# WebServer3.net
KiCad netlist of a schematic drawn in EAGLE
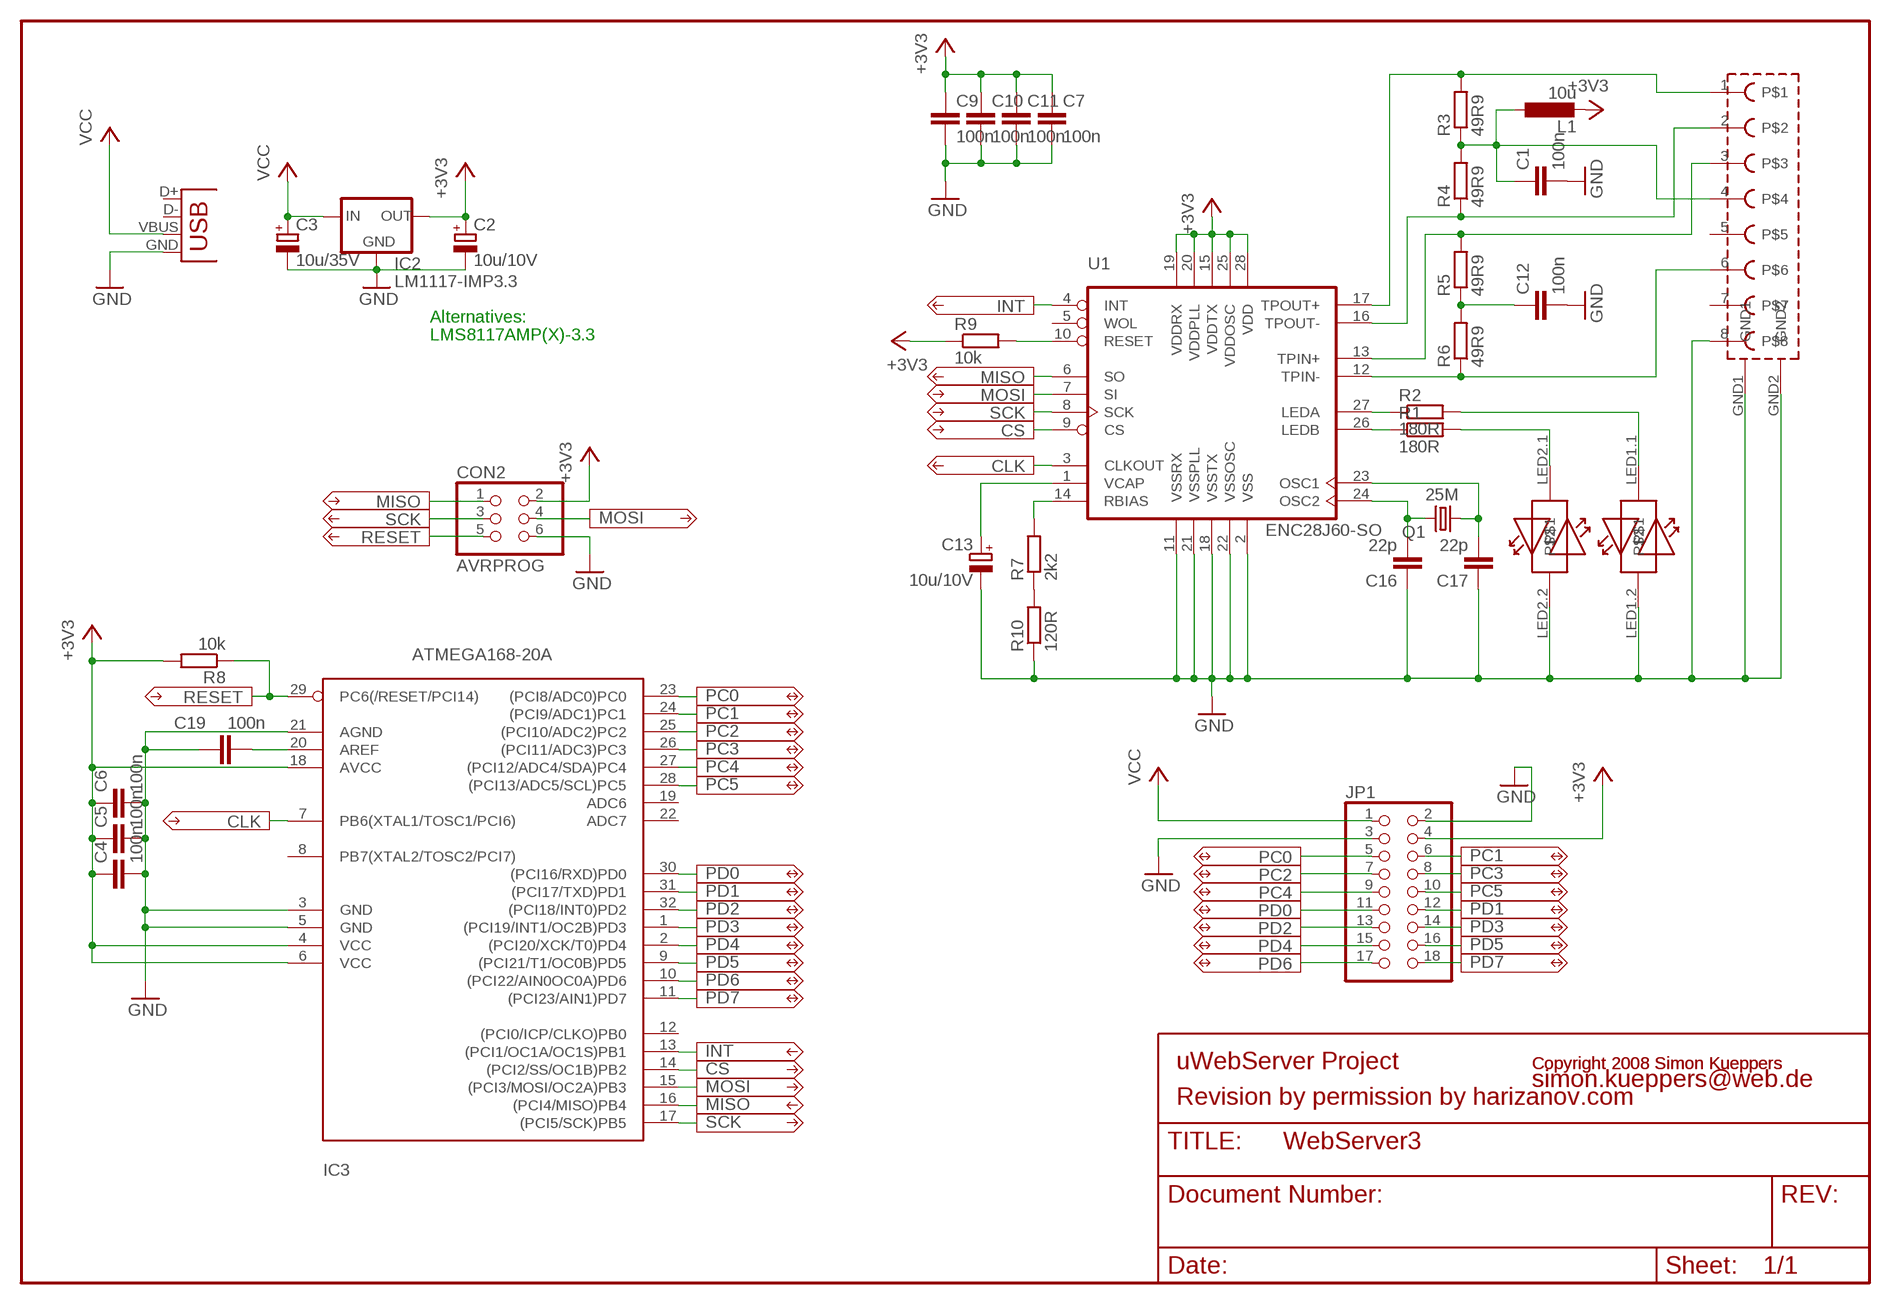
[diagram p0: schematic, sheet 1]

(export (version "E")
  (design (tool "Eeschema 10.0.6"))
  (components
    (comp (ref "C1")
      (value "100n")
      (footprint "eagle-import:C0805")
      (libsource (lib "eagle-import") (part "C-EUC0805"))
    )
    (comp (ref "C2")
      (value "10u/10V")
      (footprint "eagle-import:SMC_A")
      (libsource (lib "eagle-import") (part "CPOL-EUSMCA"))
    )
    (comp (ref "C3")
      (value "10u/35V")
      (footprint "eagle-import:SMC_C")
      (libsource (lib "eagle-import") (part "CPOL-EUSMCC"))
    )
    (comp (ref "C4")
      (value "100n")
      (footprint "eagle-import:C0805")
      (libsource (lib "eagle-import") (part "C-EUC0805"))
    )
    (comp (ref "C5")
      (value "100n")
      (footprint "eagle-import:C0805")
      (libsource (lib "eagle-import") (part "C-EUC0805"))
    )
    (comp (ref "C6")
      (value "100n")
      (footprint "eagle-import:C0805")
      (libsource (lib "eagle-import") (part "C-EUC0805"))
    )
    (comp (ref "C7")
      (value "100n")
      (footprint "eagle-import:C0805")
      (libsource (lib "eagle-import") (part "C-EUC0805"))
    )
    (comp (ref "C9")
      (value "100n")
      (footprint "eagle-import:C0805")
      (libsource (lib "eagle-import") (part "C-EUC0805"))
    )
    (comp (ref "C10")
      (value "100n")
      (footprint "eagle-import:C0805")
      (libsource (lib "eagle-import") (part "C-EUC0805"))
    )
    (comp (ref "C11")
      (value "100n")
      (footprint "eagle-import:C0805")
      (libsource (lib "eagle-import") (part "C-EUC0805"))
    )
    (comp (ref "C12")
      (value "100n")
      (footprint "eagle-import:C0805")
      (libsource (lib "eagle-import") (part "C-EUC0805"))
    )
    (comp (ref "C13")
      (value "10u/10V")
      (footprint "eagle-import:SMC_A")
      (libsource (lib "eagle-import") (part "CPOL-EUSMCA"))
    )
    (comp (ref "C16")
      (value "22p")
      (footprint "eagle-import:C0805")
      (libsource (lib "eagle-import") (part "C-EUC0805"))
    )
    (comp (ref "C17")
      (value "22p")
      (footprint "eagle-import:C0805")
      (libsource (lib "eagle-import") (part "C-EUC0805"))
    )
    (comp (ref "C19")
      (value "100n")
      (footprint "eagle-import:C0805")
      (libsource (lib "eagle-import") (part "C-EUC0805"))
    )
    (comp (ref "CON2")
      (value "AVRPROG")
      (footprint "eagle-import:2X03")
      (libsource (lib "eagle-import") (part "PINHD-2X3_2.54"))
    )
    (comp (ref "IC2")
      (value "LM1117-IMP3.3")
      (footprint "eagle-import:SOT223")
      (libsource (lib "eagle-import") (part "LM1117"))
    )
    (comp (ref "IC3")
      (value "ATMEGA168-20A")
      (footprint "eagle-import:TQFP32-08")
      (libsource (lib "eagle-import") (part "ATMEGA168A-20"))
    )
    (comp (ref "JP1")
      (value "PINHD-2X9")
      (footprint "eagle-import:2X09")
      (libsource (lib "eagle-import") (part "PINHD-2X9"))
    )
    (comp (ref "L1")
      (value "10u")
      (footprint "eagle-import:0207_10")
      (libsource (lib "eagle-import") (part "L-EU0207/10"))
    )
    (comp (ref "MAGJACK")
      (value "MAGJACK")
      (footprint "eagle-import:MAGJACK")
      (libsource (lib "eagle-import") (part "MAGJACK"))
    )
    (comp (ref "Q1")
      (value "25M")
      (footprint "eagle-import:HC49UP")
      (libsource (lib "eagle-import") (part "CRYSTALHC49UP"))
    )
    (comp (ref "R1")
      (value "180R")
      (footprint "eagle-import:R0805")
      (libsource (lib "eagle-import") (part "R-EU_R0805"))
    )
    (comp (ref "R2")
      (value "180R")
      (footprint "eagle-import:R0805")
      (libsource (lib "eagle-import") (part "R-EU_R0805"))
    )
    (comp (ref "R3")
      (value "49R9")
      (footprint "eagle-import:R0805")
      (libsource (lib "eagle-import") (part "R-EU_R0805"))
    )
    (comp (ref "R4")
      (value "49R9")
      (footprint "eagle-import:R0805")
      (libsource (lib "eagle-import") (part "R-EU_R0805"))
    )
    (comp (ref "R5")
      (value "49R9")
      (footprint "eagle-import:R0805")
      (libsource (lib "eagle-import") (part "R-EU_R0805"))
    )
    (comp (ref "R6")
      (value "49R9")
      (footprint "eagle-import:R0805")
      (libsource (lib "eagle-import") (part "R-EU_R0805"))
    )
    (comp (ref "R7")
      (value "2k2")
      (footprint "eagle-import:R0805")
      (libsource (lib "eagle-import") (part "R-EU_R0805"))
    )
    (comp (ref "R8")
      (value "10k")
      (footprint "eagle-import:R0805")
      (libsource (lib "eagle-import") (part "R-EU_R0805"))
    )
    (comp (ref "R9")
      (value "10k")
      (footprint "eagle-import:R0805")
      (libsource (lib "eagle-import") (part "R-EU_R0805"))
    )
    (comp (ref "R10")
      (value "120R")
      (footprint "eagle-import:R0805")
      (libsource (lib "eagle-import") (part "R-EU_R0805"))
    )
    (comp (ref "U1")
      (value "ENC28J60-SO")
      (footprint "eagle-import:SO28W")
      (libsource (lib "eagle-import") (part "ENC28J60-SO"))
    )
    (comp (ref "X1")
      (value "USB-MICROB")
      (footprint "eagle-import:USB-MICROB")
      (libsource (lib "eagle-import") (part "USB-MICROB"))
    )
  )
  (nets
    (net (code "1") (name "+3V3") (class "Default")
      (node (ref "C10") (pin "1") (pinfunction "1_1") (pintype "passive"))
      (node (ref "C11") (pin "1") (pinfunction "1_1") (pintype "passive"))
      (node (ref "C2") (pin "+") (pinfunction "+_+") (pintype "passive"))
      (node (ref "C4") (pin "1") (pinfunction "1_1") (pintype "passive"))
      (node (ref "C5") (pin "1") (pinfunction "1_1") (pintype "passive"))
      (node (ref "C6") (pin "1") (pinfunction "1_1") (pintype "passive"))
      (node (ref "C7") (pin "1") (pinfunction "1_1") (pintype "passive"))
      (node (ref "C9") (pin "1") (pinfunction "1_1") (pintype "passive"))
      (node (ref "CON2") (pin "2") (pinfunction "2_2") (pintype "passive"))
      (node (ref "IC2") (pin "2") (pinfunction "OUT_2") (pintype "passive"))
      (node (ref "IC3") (pin "18") (pinfunction "AVCC_18") (pintype "bidirectional"))
      (node (ref "IC3") (pin "4") (pinfunction "VCC_4") (pintype "power_in"))
      (node (ref "IC3") (pin "6") (pinfunction "VCC_6") (pintype "power_in"))
      (node (ref "JP1") (pin "4") (pinfunction "4_4") (pintype "passive"))
      (node (ref "L1") (pin "2") (pinfunction "2_2") (pintype "passive"))
      (node (ref "R8") (pin "2") (pinfunction "2_2") (pintype "passive"))
      (node (ref "R9") (pin "1") (pinfunction "1_1") (pintype "passive"))
      (node (ref "U1") (pin "15") (pinfunction "VDDTX_15") (pintype "power_in"))
      (node (ref "U1") (pin "19") (pinfunction "VDDRX_19") (pintype "power_in"))
      (node (ref "U1") (pin "20") (pinfunction "VDDPLL_20") (pintype "power_in"))
      (node (ref "U1") (pin "25") (pinfunction "VDDOSC_25") (pintype "power_in"))
      (node (ref "U1") (pin "28") (pinfunction "VDD_28") (pintype "power_in"))
    )
    (net (code "2") (name "/CLK") (class "Default")
      (node (ref "IC3") (pin "7") (pinfunction "PB6(XTAL1/TOSC1/PCI6)_7") (pintype "bidirectional"))
      (node (ref "U1") (pin "3") (pinfunction "CLKOUT_3") (pintype "output"))
    )
    (net (code "3") (name "/CS") (class "Default")
      (node (ref "IC3") (pin "14") (pinfunction "(PCI2/SS/OC1B)PB2_14") (pintype "bidirectional"))
      (node (ref "U1") (pin "9") (pinfunction "CS_9") (pintype "input"))
    )
    (net (code "4") (name "/INT") (class "Default")
      (node (ref "IC3") (pin "13") (pinfunction "(PCI1/OC1A/OC1S)PB1_13") (pintype "bidirectional"))
      (node (ref "U1") (pin "4") (pinfunction "INT_4") (pintype "output"))
    )
    (net (code "5") (name "/MISO") (class "Default")
      (node (ref "CON2") (pin "1") (pinfunction "1_1") (pintype "passive"))
      (node (ref "IC3") (pin "16") (pinfunction "(PCI4/MISO)PB4_16") (pintype "bidirectional"))
      (node (ref "U1") (pin "6") (pinfunction "SO_6") (pintype "output"))
    )
    (net (code "6") (name "/MOSI") (class "Default")
      (node (ref "CON2") (pin "4") (pinfunction "4_4") (pintype "passive"))
      (node (ref "IC3") (pin "15") (pinfunction "(PCI3/MOSI/OC2A)PB3_15") (pintype "bidirectional"))
      (node (ref "U1") (pin "7") (pinfunction "SI_7") (pintype "input"))
    )
    (net (code "7") (name "/PC0") (class "Default")
      (node (ref "IC3") (pin "23") (pinfunction "(PCI8/ADC0)PC0_23") (pintype "bidirectional"))
      (node (ref "JP1") (pin "5") (pinfunction "5_5") (pintype "passive"))
    )
    (net (code "8") (name "/PC1") (class "Default")
      (node (ref "IC3") (pin "24") (pinfunction "(PCI9/ADC1)PC1_24") (pintype "bidirectional"))
      (node (ref "JP1") (pin "6") (pinfunction "6_6") (pintype "passive"))
    )
    (net (code "9") (name "/PC2") (class "Default")
      (node (ref "IC3") (pin "25") (pinfunction "(PCI10/ADC2)PC2_25") (pintype "bidirectional"))
      (node (ref "JP1") (pin "7") (pinfunction "7_7") (pintype "passive"))
    )
    (net (code "10") (name "/PC3") (class "Default")
      (node (ref "IC3") (pin "26") (pinfunction "(PCI11/ADC3)PC3_26") (pintype "bidirectional"))
      (node (ref "JP1") (pin "8") (pinfunction "8_8") (pintype "passive"))
    )
    (net (code "11") (name "/PC4") (class "Default")
      (node (ref "IC3") (pin "27") (pinfunction "(PCI12/ADC4/SDA)PC4_27") (pintype "bidirectional"))
      (node (ref "JP1") (pin "9") (pinfunction "9_9") (pintype "passive"))
    )
    (net (code "12") (name "/PC5") (class "Default")
      (node (ref "IC3") (pin "28") (pinfunction "(PCI13/ADC5/SCL)PC5_28") (pintype "bidirectional"))
      (node (ref "JP1") (pin "10") (pinfunction "10_10") (pintype "passive"))
    )
    (net (code "13") (name "/PD0") (class "Default")
      (node (ref "IC3") (pin "30") (pinfunction "(PCI16/RXD)PD0_30") (pintype "bidirectional"))
      (node (ref "JP1") (pin "11") (pinfunction "11_11") (pintype "passive"))
    )
    (net (code "14") (name "/PD1") (class "Default")
      (node (ref "IC3") (pin "31") (pinfunction "(PCI17/TXD)PD1_31") (pintype "bidirectional"))
      (node (ref "JP1") (pin "12") (pinfunction "12_12") (pintype "passive"))
    )
    (net (code "15") (name "/PD2") (class "Default")
      (node (ref "IC3") (pin "32") (pinfunction "(PCI18/INT0)PD2_32") (pintype "bidirectional"))
      (node (ref "JP1") (pin "13") (pinfunction "13_13") (pintype "passive"))
    )
    (net (code "16") (name "/PD3") (class "Default")
      (node (ref "IC3") (pin "1") (pinfunction "(PCI19/INT1/OC2B)PD3_1") (pintype "bidirectional"))
      (node (ref "JP1") (pin "14") (pinfunction "14_14") (pintype "passive"))
    )
    (net (code "17") (name "/PD4") (class "Default")
      (node (ref "IC3") (pin "2") (pinfunction "(PCI20/XCK/T0)PD4_2") (pintype "bidirectional"))
      (node (ref "JP1") (pin "15") (pinfunction "15_15") (pintype "passive"))
    )
    (net (code "18") (name "/PD5") (class "Default")
      (node (ref "IC3") (pin "9") (pinfunction "(PCI21/T1/OC0B)PD5_9") (pintype "bidirectional"))
      (node (ref "JP1") (pin "16") (pinfunction "16_16") (pintype "passive"))
    )
    (net (code "19") (name "/PD6") (class "Default")
      (node (ref "IC3") (pin "10") (pinfunction "(PCI22/AIN0OC0A)PD6_10") (pintype "bidirectional"))
      (node (ref "JP1") (pin "17") (pinfunction "17_17") (pintype "passive"))
    )
    (net (code "20") (name "/PD7") (class "Default")
      (node (ref "IC3") (pin "11") (pinfunction "(PCI23/AIN1)PD7_11") (pintype "bidirectional"))
      (node (ref "JP1") (pin "18") (pinfunction "18_18") (pintype "passive"))
    )
    (net (code "21") (name "/RESET") (class "Default")
      (node (ref "CON2") (pin "5") (pinfunction "5_5") (pintype "passive"))
      (node (ref "IC3") (pin "29") (pinfunction "PC6(/RESET/PCI14)_29") (pintype "bidirectional"))
      (node (ref "R8") (pin "1") (pinfunction "1_1") (pintype "passive"))
    )
    (net (code "22") (name "/SCK") (class "Default")
      (node (ref "CON2") (pin "3") (pinfunction "3_3") (pintype "passive"))
      (node (ref "IC3") (pin "17") (pinfunction "(PCI5/SCK)PB5_17") (pintype "bidirectional"))
      (node (ref "U1") (pin "8") (pinfunction "SCK_8") (pintype "input"))
    )
    (net (code "23") (name "GND") (class "Default")
      (node (ref "C1") (pin "2") (pinfunction "2_2") (pintype "passive"))
      (node (ref "C10") (pin "2") (pinfunction "2_2") (pintype "passive"))
      (node (ref "C11") (pin "2") (pinfunction "2_2") (pintype "passive"))
      (node (ref "C12") (pin "2") (pinfunction "2_2") (pintype "passive"))
      (node (ref "C13") (pin "-") (pinfunction "-_-") (pintype "passive"))
      (node (ref "C16") (pin "1") (pinfunction "1_1") (pintype "passive"))
      (node (ref "C17") (pin "1") (pinfunction "1_1") (pintype "passive"))
      (node (ref "C19") (pin "1") (pinfunction "1_1") (pintype "passive"))
      (node (ref "C2") (pin "-") (pinfunction "-_-") (pintype "passive"))
      (node (ref "C3") (pin "-") (pinfunction "-_-") (pintype "passive"))
      (node (ref "C4") (pin "2") (pinfunction "2_2") (pintype "passive"))
      (node (ref "C5") (pin "2") (pinfunction "2_2") (pintype "passive"))
      (node (ref "C6") (pin "2") (pinfunction "2_2") (pintype "passive"))
      (node (ref "C7") (pin "2") (pinfunction "2_2") (pintype "passive"))
      (node (ref "C9") (pin "2") (pinfunction "2_2") (pintype "passive"))
      (node (ref "CON2") (pin "6") (pinfunction "6_6") (pintype "passive"))
      (node (ref "IC2") (pin "1") (pinfunction "GND_1") (pintype "input"))
      (node (ref "IC3") (pin "21") (pinfunction "AGND_21") (pintype "bidirectional"))
      (node (ref "IC3") (pin "3") (pinfunction "GND_3") (pintype "power_in"))
      (node (ref "IC3") (pin "5") (pinfunction "GND_5") (pintype "power_in"))
      (node (ref "JP1") (pin "2") (pinfunction "2_2") (pintype "passive"))
      (node (ref "JP1") (pin "3") (pinfunction "3_3") (pintype "passive"))
      (node (ref "MAGJACK") (pin "8") (pinfunction "P$8_8") (pintype "passive"))
      (node (ref "MAGJACK") (pin "GND1") (pinfunction "GND1_GND1") (pintype "passive"))
      (node (ref "MAGJACK") (pin "GND2") (pinfunction "GND2_GND2") (pintype "passive"))
      (node (ref "MAGJACK") (pin "LED1.2") (pinfunction "P$2_LED1.2") (pintype "passive"))
      (node (ref "MAGJACK") (pin "LED2.2") (pinfunction "P$2_LED2.2") (pintype "passive"))
      (node (ref "R10") (pin "1") (pinfunction "1_1") (pintype "passive"))
      (node (ref "U1") (pin "11") (pinfunction "VSSRX_11") (pintype "power_in"))
      (node (ref "U1") (pin "18") (pinfunction "VSSTX_18") (pintype "power_in"))
      (node (ref "U1") (pin "2") (pinfunction "VSS_2") (pintype "power_in"))
      (node (ref "U1") (pin "21") (pinfunction "VSSPLL_21") (pintype "power_in"))
      (node (ref "U1") (pin "22") (pinfunction "VSSOSC_22") (pintype "power_in"))
      (node (ref "X1") (pin "GND") (pinfunction "GND_GND") (pintype "bidirectional"))
    )
    (net (code "24") (name "Net-(C12-Pad1)") (class "Default")
      (node (ref "C12") (pin "1") (pinfunction "1_1") (pintype "passive"))
      (node (ref "R5") (pin "1") (pinfunction "1_1") (pintype "passive"))
      (node (ref "R6") (pin "2") (pinfunction "2_2") (pintype "passive"))
    )
    (net (code "25") (name "Net-(IC3-AREF)") (class "Default")
      (node (ref "C19") (pin "2") (pinfunction "2_2") (pintype "passive"))
      (node (ref "IC3") (pin "20") (pinfunction "AREF_20") (pintype "bidirectional"))
    )
    (net (code "26") (name "Net-(MAGJACKA-P$1)") (class "Default")
      (node (ref "MAGJACK") (pin "1") (pinfunction "P$1_1") (pintype "passive"))
      (node (ref "R3") (pin "2") (pinfunction "2_2") (pintype "passive"))
      (node (ref "U1") (pin "17") (pinfunction "TPOUT+_17") (pintype "output"))
    )
    (net (code "27") (name "Net-(MAGJACKA-P$2)") (class "Default")
      (node (ref "MAGJACK") (pin "2") (pinfunction "P$2_2") (pintype "passive"))
      (node (ref "R4") (pin "1") (pinfunction "1_1") (pintype "passive"))
      (node (ref "U1") (pin "16") (pinfunction "TPOUT-_16") (pintype "output"))
    )
    (net (code "28") (name "Net-(MAGJACKA-P$3)") (class "Default")
      (node (ref "MAGJACK") (pin "3") (pinfunction "P$3_3") (pintype "passive"))
      (node (ref "R5") (pin "2") (pinfunction "2_2") (pintype "passive"))
      (node (ref "U1") (pin "13") (pinfunction "TPIN+_13") (pintype "input"))
    )
    (net (code "29") (name "Net-(MAGJACKA-P$4)") (class "Default")
      (node (ref "C1") (pin "1") (pinfunction "1_1") (pintype "passive"))
      (node (ref "L1") (pin "1") (pinfunction "1_1") (pintype "passive"))
      (node (ref "MAGJACK") (pin "4") (pinfunction "P$4_4") (pintype "passive"))
      (node (ref "R3") (pin "1") (pinfunction "1_1") (pintype "passive"))
      (node (ref "R4") (pin "2") (pinfunction "2_2") (pintype "passive"))
    )
    (net (code "30") (name "Net-(MAGJACKA-P$6)") (class "Default")
      (node (ref "MAGJACK") (pin "6") (pinfunction "P$6_6") (pintype "passive"))
      (node (ref "R6") (pin "1") (pinfunction "1_1") (pintype "passive"))
      (node (ref "U1") (pin "12") (pinfunction "TPIN-_12") (pintype "input"))
    )
    (net (code "31") (name "Net-(MAGJACKB-P$1)") (class "Default")
      (node (ref "MAGJACK") (pin "LED1.1") (pinfunction "P$1_LED1.1") (pintype "passive"))
      (node (ref "R2") (pin "2") (pinfunction "2_2") (pintype "passive"))
    )
    (net (code "32") (name "Net-(MAGJACKC-P$1)") (class "Default")
      (node (ref "MAGJACK") (pin "LED2.1") (pinfunction "P$1_LED2.1") (pintype "passive"))
      (node (ref "R1") (pin "2") (pinfunction "2_2") (pintype "passive"))
    )
    (net (code "33") (name "Net-(R10-Pad2)") (class "Default")
      (node (ref "R10") (pin "2") (pinfunction "2_2") (pintype "passive"))
      (node (ref "R7") (pin "1") (pinfunction "1_1") (pintype "passive"))
    )
    (net (code "34") (name "Net-(U1-LEDA)") (class "Default")
      (node (ref "R2") (pin "1") (pinfunction "1_1") (pintype "passive"))
      (node (ref "U1") (pin "27") (pinfunction "LEDA_27") (pintype "output"))
    )
    (net (code "35") (name "Net-(U1-LEDB)") (class "Default")
      (node (ref "R1") (pin "1") (pinfunction "1_1") (pintype "passive"))
      (node (ref "U1") (pin "26") (pinfunction "LEDB_26") (pintype "output"))
    )
    (net (code "36") (name "Net-(U1-OSC1)") (class "Default")
      (node (ref "C17") (pin "2") (pinfunction "2_2") (pintype "passive"))
      (node (ref "Q1") (pin "1") (pinfunction "1_1") (pintype "passive"))
      (node (ref "U1") (pin "23") (pinfunction "OSC1_23") (pintype "input"))
    )
    (net (code "37") (name "Net-(U1-OSC2)") (class "Default")
      (node (ref "C16") (pin "2") (pinfunction "2_2") (pintype "passive"))
      (node (ref "Q1") (pin "2") (pinfunction "2_2") (pintype "passive"))
      (node (ref "U1") (pin "24") (pinfunction "OSC2_24") (pintype "output"))
    )
    (net (code "38") (name "Net-(U1-RBIAS)") (class "Default")
      (node (ref "R7") (pin "2") (pinfunction "2_2") (pintype "passive"))
      (node (ref "U1") (pin "14") (pinfunction "RBIAS_14") (pintype "passive"))
    )
    (net (code "39") (name "Net-(U1-RESET)") (class "Default")
      (node (ref "R9") (pin "2") (pinfunction "2_2") (pintype "passive"))
      (node (ref "U1") (pin "10") (pinfunction "RESET_10") (pintype "input"))
    )
    (net (code "40") (name "Net-(U1-VCAP)") (class "Default")
      (node (ref "C13") (pin "+") (pinfunction "+_+") (pintype "passive"))
      (node (ref "U1") (pin "1") (pinfunction "VCAP_1") (pintype "power_in"))
    )
    (net (code "41") (name "VCC") (class "Default")
      (node (ref "C3") (pin "+") (pinfunction "+_+") (pintype "passive"))
      (node (ref "IC2") (pin "3") (pinfunction "IN_3") (pintype "input"))
      (node (ref "JP1") (pin "1") (pinfunction "1_1") (pintype "passive"))
      (node (ref "X1") (pin "VBUS") (pinfunction "VBUS_VBUS") (pintype "bidirectional"))
    )
    (net (code "42") (name "unconnected-(IC3-(PCI0{slash}ICP{slash}CLKO)PB0-Pad12)") (class "Default")
      (node (ref "IC3") (pin "12") (pinfunction "(PCI0/ICP/CLKO)PB0_12") (pintype "bidirectional"))
    )
    (net (code "43") (name "unconnected-(IC3-ADC6-Pad19)") (class "Default")
      (node (ref "IC3") (pin "19") (pinfunction "ADC6_19") (pintype "bidirectional"))
    )
    (net (code "44") (name "unconnected-(IC3-ADC7-Pad22)") (class "Default")
      (node (ref "IC3") (pin "22") (pinfunction "ADC7_22") (pintype "bidirectional"))
    )
    (net (code "45") (name "unconnected-(IC3-PB7(XTAL2{slash}TOSC2{slash}PCI7)-Pad8)") (class "Default")
      (node (ref "IC3") (pin "8") (pinfunction "PB7(XTAL2/TOSC2/PCI7)_8") (pintype "bidirectional"))
    )
    (net (code "46") (name "unconnected-(MAGJACKA-P$5-Pad5)") (class "Default")
      (node (ref "MAGJACK") (pin "5") (pinfunction "P$5_5") (pintype "passive"))
    )
    (net (code "47") (name "unconnected-(MAGJACKA-P$7-Pad7)") (class "Default")
      (node (ref "MAGJACK") (pin "7") (pinfunction "P$7_7") (pintype "passive"))
    )
    (net (code "48") (name "unconnected-(U1-WOL-Pad5)") (class "Default")
      (node (ref "U1") (pin "5") (pinfunction "WOL_5") (pintype "output"))
    )
    (net (code "49") (name "unconnected-(X1-PadD+)") (class "Default")
      (node (ref "X1") (pin "D+") (pinfunction "D+_D+") (pintype "bidirectional"))
    )
    (net (code "50") (name "unconnected-(X1-PadD-)") (class "Default")
      (node (ref "X1") (pin "D-") (pinfunction "D-_D-") (pintype "bidirectional"))
    )
  )
)
